# SPCE061A.net
KiCad netlist of a schematic drawn in Altium Designer
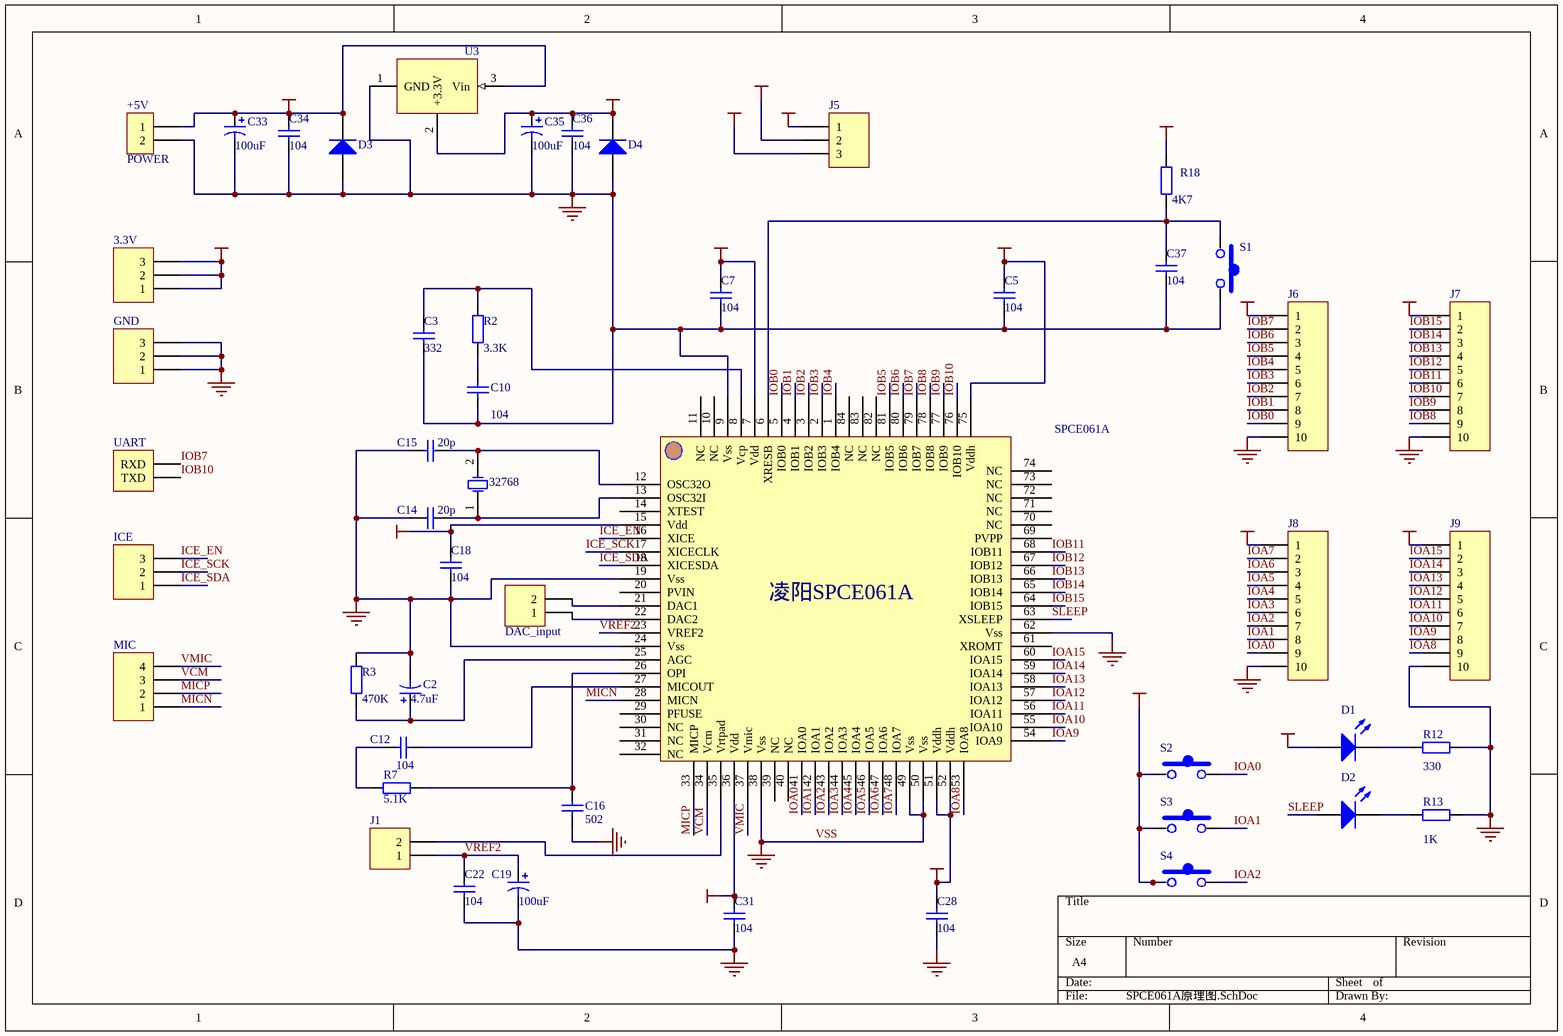
[diagram p0: SPCE061A原理图.SchDoc]

(export (version "E")
  (design (tool "Eeschema 10.0.6"))
  (components
    (comp (ref "+5V")
      (value "POWER")
      (footprint "zxcourhc:HDR-2")
      (libsource (lib "OldCow1 (1)") (part "POWER"))
    )
    (comp (ref "3.3V")
      (value "Header 3")
      (footprint "HDR1X3")
      (description "Header, 3-Pin")
      (fields (field (name "PUBLISHER") "Altium Limited"))
      (libsource (lib "Miscellaneous Connectors") (part "Header 3"))
    )
    (comp (ref "32768")
      (value "XTAL")
      (footprint "BCY-W2/D3.1")
      (description "Crystal Oscillator")
      (fields (field (name "PUBLISHER") "Altium Limited"))
      (libsource (lib "Miscellaneous Devices") (part "XTAL"))
    )
    (comp (ref "C2")
      (value "4.7uF")
      (footprint "zxcourhc:C-DJ-4")
      (description "Polarized Capacitor (Radial)")
      (fields (field (name "Comment") "Cap Pol1") (field (name "PUBLISHER") "Altium Limited"))
      (libsource (lib "Miscellaneous Devices") (part "Cap Pol1"))
    )
    (comp (ref "C3")
      (value "332")
      (footprint "Miscellaneous Devices:CAPR2.54-5.1x3.2")
      (description "Capacitor")
      (fields (field (name "Comment") "Cap") (field (name "PUBLISHER") "Altium Limited"))
      (libsource (lib "Miscellaneous Devices") (part "Cap"))
    )
    (comp (ref "C5")
      (value "104")
      (footprint "Miscellaneous Devices:CAPR2.54-5.1x3.2")
      (description "Capacitor")
      (fields (field (name "Comment") "Cap") (field (name "PUBLISHER") "Altium Limited"))
      (libsource (lib "Miscellaneous Devices") (part "Cap"))
    )
    (comp (ref "C7")
      (value "104")
      (footprint "Miscellaneous Devices:CAPR2.54-5.1x3.2")
      (description "Capacitor")
      (fields (field (name "Comment") "Cap") (field (name "PUBLISHER") "Altium Limited"))
      (libsource (lib "Miscellaneous Devices") (part "Cap"))
    )
    (comp (ref "C10")
      (value "104")
      (footprint "Miscellaneous Devices:CAPR2.54-5.1x3.2")
      (description "Capacitor")
      (fields (field (name "Comment") "Cap") (field (name "PUBLISHER") "Altium Limited"))
      (libsource (lib "Miscellaneous Devices") (part "Cap"))
    )
    (comp (ref "C12")
      (value "104")
      (footprint "Miscellaneous Devices:CAPR2.54-5.1x3.2")
      (description "Capacitor")
      (fields (field (name "Comment") "Cap") (field (name "PUBLISHER") "Altium Limited"))
      (libsource (lib "Miscellaneous Devices") (part "Cap"))
    )
    (comp (ref "C14")
      (value "20p")
      (footprint "Miscellaneous Devices:CAPR2.54-5.1x3.2")
      (description "Capacitor")
      (fields (field (name "Comment") "Cap") (field (name "PUBLISHER") "Altium Limited"))
      (libsource (lib "Miscellaneous Devices") (part "Cap"))
    )
    (comp (ref "C15")
      (value "20p")
      (footprint "Miscellaneous Devices:CAPR2.54-5.1x3.2")
      (description "Capacitor")
      (fields (field (name "Comment") "Cap") (field (name "PUBLISHER") "Altium Limited"))
      (libsource (lib "Miscellaneous Devices") (part "Cap"))
    )
    (comp (ref "C16")
      (value "502")
      (footprint "Miscellaneous Devices:CAPR2.54-5.1x3.2")
      (description "Capacitor")
      (fields (field (name "Comment") "Cap") (field (name "PUBLISHER") "Altium Limited"))
      (libsource (lib "Miscellaneous Devices") (part "Cap"))
    )
    (comp (ref "C18")
      (value "104")
      (footprint "Miscellaneous Devices:CAPR2.54-5.1x3.2")
      (description "Capacitor")
      (fields (field (name "Comment") "Cap") (field (name "PUBLISHER") "Altium Limited"))
      (libsource (lib "Miscellaneous Devices") (part "Cap"))
    )
    (comp (ref "C19")
      (value "100uF")
      (footprint "zxcourhc:C-DJ-4")
      (description "Polarized Capacitor (Radial)")
      (fields (field (name "Comment") "Cap Pol1") (field (name "PUBLISHER") "Altium Limited"))
      (libsource (lib "Miscellaneous Devices") (part "Cap Pol1"))
    )
    (comp (ref "C22")
      (value "104")
      (footprint "Miscellaneous Devices:CAPR2.54-5.1x3.2")
      (description "Capacitor")
      (fields (field (name "Comment") "Cap") (field (name "PUBLISHER") "Altium Limited"))
      (libsource (lib "Miscellaneous Devices") (part "Cap"))
    )
    (comp (ref "C28")
      (value "104")
      (footprint "Miscellaneous Devices:CAPR2.54-5.1x3.2")
      (description "Capacitor")
      (fields (field (name "Comment") "Cap") (field (name "PUBLISHER") "Altium Limited"))
      (libsource (lib "Miscellaneous Devices") (part "Cap"))
    )
    (comp (ref "C31")
      (value "104")
      (footprint "Miscellaneous Devices:CAPR2.54-5.1x3.2")
      (description "Capacitor")
      (fields (field (name "Comment") "Cap") (field (name "PUBLISHER") "Altium Limited"))
      (libsource (lib "Miscellaneous Devices") (part "Cap"))
    )
    (comp (ref "C33")
      (value "100uF")
      (footprint "zxcourhc:C-DJ-4")
      (description "Polarized Capacitor (Radial)")
      (fields (field (name "Comment") "Cap Pol1") (field (name "PUBLISHER") "Altium Limited"))
      (libsource (lib "Miscellaneous Devices") (part "Cap Pol1"))
    )
    (comp (ref "C34")
      (value "104")
      (footprint "Miscellaneous Devices:CAPR2.54-5.1x3.2")
      (description "Capacitor")
      (fields (field (name "Comment") "Cap") (field (name "PUBLISHER") "Altium Limited"))
      (libsource (lib "Miscellaneous Devices") (part "Cap"))
    )
    (comp (ref "C35")
      (value "100uF")
      (footprint "zxcourhc:C-DJ-4")
      (description "Polarized Capacitor (Radial)")
      (fields (field (name "Comment") "Cap Pol1") (field (name "PUBLISHER") "Altium Limited"))
      (libsource (lib "Miscellaneous Devices") (part "Cap Pol1"))
    )
    (comp (ref "C36")
      (value "104")
      (footprint "Miscellaneous Devices:CAPR2.54-5.1x3.2")
      (description "Capacitor")
      (fields (field (name "Comment") "Cap") (field (name "PUBLISHER") "Altium Limited"))
      (libsource (lib "Miscellaneous Devices") (part "Cap"))
    )
    (comp (ref "C37")
      (value "104")
      (footprint "Miscellaneous Devices:CAPR2.54-5.1x3.2")
      (description "Capacitor")
      (fields (field (name "Comment") "Cap") (field (name "PUBLISHER") "Altium Limited"))
      (libsource (lib "Miscellaneous Devices") (part "Cap"))
    )
    (comp (ref "D1")
      (value "LED3")
      (footprint "SMD _LED")
      (description "Typical BLUE SiC LED")
      (fields (field (name "PUBLISHER") "Altium Limited"))
      (libsource (lib "Miscellaneous Devices") (part "LED3"))
    )
    (comp (ref "D2")
      (value "LED3")
      (footprint "SMD _LED")
      (description "Typical BLUE SiC LED")
      (fields (field (name "PUBLISHER") "Altium Limited"))
      (libsource (lib "Miscellaneous Devices") (part "LED3"))
    )
    (comp (ref "D3")
      (value "Diode 1N4148")
      (footprint "DIO7.1-3.9x1.9")
      (description "High Conductance Fast Diode")
      (fields (field (name "PUBLISHER") "Altium Limited"))
      (libsource (lib "Miscellaneous Devices") (part "Diode 1N4148"))
    )
    (comp (ref "D4")
      (value "Diode 1N4148")
      (footprint "DIO7.1-3.9x1.9")
      (description "High Conductance Fast Diode")
      (fields (field (name "PUBLISHER") "Altium Limited"))
      (libsource (lib "Miscellaneous Devices") (part "Diode 1N4148"))
    )
    (comp (ref "DAC_input")
      (value "Header 2")
      (footprint "HDR1X2")
      (description "Header, 2-Pin")
      (fields (field (name "PUBLISHER") "Altium Limited"))
      (libsource (lib "Miscellaneous Connectors") (part "Header 2"))
    )
    (comp (ref "GND")
      (value "Header 3")
      (footprint "HDR1X3")
      (description "Header, 3-Pin")
      (fields (field (name "PUBLISHER") "Altium Limited"))
      (libsource (lib "Miscellaneous Connectors") (part "Header 3"))
    )
    (comp (ref "ICE")
      (value "Header 3")
      (footprint "HDR1X3")
      (description "Header, 3-Pin")
      (fields (field (name "PUBLISHER") "Altium Limited"))
      (libsource (lib "Miscellaneous Connectors") (part "Header 3"))
    )
    (comp (ref "J1")
      (value "Header 2")
      (footprint "HDR1X2")
      (description "Header, 2-Pin")
      (fields (field (name "PUBLISHER") "Altium Limited"))
      (libsource (lib "Miscellaneous Connectors") (part "Header 2"))
    )
    (comp (ref "J5")
      (value "Header 3")
      (footprint "HDR1X3")
      (description "Header, 3-Pin")
      (fields (field (name "PUBLISHER") "Altium Limited"))
      (libsource (lib "") (part "Header 3_1"))
    )
    (comp (ref "J6")
      (value "IOB0~IOB7")
      (footprint "HDR1X10")
      (description "Header, 10-Pin")
      (fields (field (name "PUBLISHER") "Altium Limited"))
      (libsource (lib "Miscellaneous Connectors") (part "Header 10"))
    )
    (comp (ref "J7")
      (value "IOB8~IOB15")
      (footprint "HDR1X10")
      (description "Header, 10-Pin")
      (fields (field (name "PUBLISHER") "Altium Limited"))
      (libsource (lib "Miscellaneous Connectors") (part "Header 10"))
    )
    (comp (ref "J8")
      (value "IOA0~IOA7")
      (footprint "HDR1X10")
      (description "Header, 10-Pin")
      (fields (field (name "PUBLISHER") "Altium Limited"))
      (libsource (lib "Miscellaneous Connectors") (part "Header 10"))
    )
    (comp (ref "J9")
      (value "IOA8~IOA15")
      (footprint "HDR1X10")
      (description "Header, 10-Pin")
      (fields (field (name "PUBLISHER") "Altium Limited"))
      (libsource (lib "Miscellaneous Connectors") (part "Header 10"))
    )
    (comp (ref "MIC")
      (value "Header 4")
      (footprint "HDR1X4")
      (description "Header, 4-Pin")
      (fields (field (name "PUBLISHER") "Altium Limited"))
      (libsource (lib "Miscellaneous Connectors") (part "Header 4"))
    )
    (comp (ref "R2")
      (value "3.3K")
      (footprint "AXIAL-0.4")
      (description "Resistor")
      (fields (field (name "Comment") "Res2") (field (name "PUBLISHER") "Altium Limited"))
      (libsource (lib "") (part "Res2_2"))
    )
    (comp (ref "R3")
      (value "470K")
      (footprint "AXIAL-0.4")
      (description "Resistor")
      (fields (field (name "Comment") "Res2") (field (name "PUBLISHER") "Altium Limited"))
      (libsource (lib "") (part "Res2_2"))
    )
    (comp (ref "R7")
      (value "5.1K")
      (footprint "AXIAL-0.4")
      (description "Resistor")
      (fields (field (name "Comment") "Res2") (field (name "PUBLISHER") "Altium Limited"))
      (libsource (lib "") (part "Res2_1"))
    )
    (comp (ref "R12")
      (value "330")
      (footprint "AXIAL-0.4")
      (description "Resistor")
      (fields (field (name "Comment") "Res2") (field (name "PUBLISHER") "Altium Limited"))
      (libsource (lib "Miscellaneous Devices") (part "Res2"))
    )
    (comp (ref "R13")
      (value "1K")
      (footprint "AXIAL-0.4")
      (description "Resistor")
      (fields (field (name "Comment") "Res2") (field (name "PUBLISHER") "Altium Limited"))
      (libsource (lib "Miscellaneous Devices") (part "Res2"))
    )
    (comp (ref "R18")
      (value "4K7")
      (footprint "AXIAL-0.4")
      (description "Resistor")
      (fields (field (name "Comment") "Res2") (field (name "PUBLISHER") "Altium Limited"))
      (libsource (lib "") (part "Res2_2"))
    )
    (comp (ref "S1") (value "KEY") (footprint "an-6*6") (libsource (lib "OldCow1 (1)") (part "KEY")))
    (comp (ref "S2")
      (value "KEY2")
      (footprint "zxcourhc:an-6*6")
      (libsource (lib "OldCow1 (1)") (part "KEY"))
    )
    (comp (ref "S3") (value "KEY3") (footprint "an-6*6") (libsource (lib "OldCow1 (1)") (part "KEY")))
    (comp (ref "S4") (value "KEY4") (footprint "an-6*6") (libsource (lib "OldCow1 (1)") (part "KEY")))
    (comp (ref "SPCE061A")
      (value "PLCC84")
      (footprint "SPCE061A_PLCC84")
      (libsource (lib "SPCE061A") (part "SPCE061A_PLCC84"))
    )
    (comp (ref "U3") (value "LM7833") (footprint "A1117") (libsource (lib "MyInt_Lib") (part "LM7805CT")))
    (comp (ref "UART")
      (value "Header 2")
      (footprint "HDR1X2")
      (description "Header, 2-Pin")
      (fields (field (name "PUBLISHER") "Altium Limited"))
      (libsource (lib "Miscellaneous Connectors") (part "Header 2"))
    )
  )
  (nets
    (net (code "1") (name "/ICE_EN") (class "Default")
      (node (ref "ICE") (pin "3") (pinfunction "3_3") (pintype "passive"))
      (node (ref "SPCE061A") (pin "16") (pinfunction "XICE_16") (pintype "passive"))
    )
    (net (code "2") (name "/ICE_SCK") (class "Default")
      (node (ref "ICE") (pin "2") (pinfunction "2_2") (pintype "passive"))
      (node (ref "SPCE061A") (pin "17") (pinfunction "XICECLK_17") (pintype "passive"))
    )
    (net (code "3") (name "/ICE_SDA") (class "Default")
      (node (ref "ICE") (pin "1") (pinfunction "1_1") (pintype "passive"))
      (node (ref "SPCE061A") (pin "18") (pinfunction "XICESDA_18") (pintype "passive"))
    )
    (net (code "4") (name "/IOA0") (class "Default")
      (node (ref "J8") (pin "9") (pinfunction "9_9") (pintype "passive"))
      (node (ref "S2") (pin "2") (pinfunction "2_2") (pintype "passive"))
      (node (ref "SPCE061A") (pin "41") (pinfunction "IOA0_41") (pintype "passive"))
    )
    (net (code "5") (name "/IOA1") (class "Default")
      (node (ref "J8") (pin "8") (pinfunction "8_8") (pintype "passive"))
      (node (ref "S3") (pin "2") (pinfunction "2_2") (pintype "passive"))
      (node (ref "SPCE061A") (pin "42") (pinfunction "IOA1_42") (pintype "passive"))
    )
    (net (code "6") (name "/IOA2") (class "Default")
      (node (ref "J8") (pin "7") (pinfunction "7_7") (pintype "passive"))
      (node (ref "S4") (pin "2") (pinfunction "2_2") (pintype "passive"))
      (node (ref "SPCE061A") (pin "43") (pinfunction "IOA2_43") (pintype "passive"))
    )
    (net (code "7") (name "/IOA3") (class "Default")
      (node (ref "J8") (pin "6") (pinfunction "6_6") (pintype "passive"))
      (node (ref "SPCE061A") (pin "44") (pinfunction "IOA3_44") (pintype "passive"))
    )
    (net (code "8") (name "/IOA4") (class "Default")
      (node (ref "J8") (pin "5") (pinfunction "5_5") (pintype "passive"))
      (node (ref "SPCE061A") (pin "45") (pinfunction "IOA4_45") (pintype "passive"))
    )
    (net (code "9") (name "/IOA5") (class "Default")
      (node (ref "J8") (pin "4") (pinfunction "4_4") (pintype "passive"))
      (node (ref "SPCE061A") (pin "46") (pinfunction "IOA5_46") (pintype "passive"))
    )
    (net (code "10") (name "/IOA6") (class "Default")
      (node (ref "J8") (pin "3") (pinfunction "3_3") (pintype "passive"))
      (node (ref "SPCE061A") (pin "47") (pinfunction "IOA6_47") (pintype "passive"))
    )
    (net (code "11") (name "/IOA7") (class "Default")
      (node (ref "J8") (pin "2") (pinfunction "2_2") (pintype "passive"))
      (node (ref "SPCE061A") (pin "48") (pinfunction "IOA7_48") (pintype "passive"))
    )
    (net (code "12") (name "/IOA8") (class "Default")
      (node (ref "J9") (pin "9") (pinfunction "9_9") (pintype "passive"))
      (node (ref "SPCE061A") (pin "53") (pinfunction "IOA8_53") (pintype "passive"))
    )
    (net (code "13") (name "/IOA9") (class "Default")
      (node (ref "J9") (pin "8") (pinfunction "8_8") (pintype "passive"))
      (node (ref "SPCE061A") (pin "54") (pinfunction "IOA9_54") (pintype "passive"))
    )
    (net (code "14") (name "/IOA10") (class "Default")
      (node (ref "J9") (pin "7") (pinfunction "7_7") (pintype "passive"))
      (node (ref "SPCE061A") (pin "55") (pinfunction "IOA10_55") (pintype "passive"))
    )
    (net (code "15") (name "/IOA11") (class "Default")
      (node (ref "J9") (pin "6") (pinfunction "6_6") (pintype "passive"))
      (node (ref "SPCE061A") (pin "56") (pinfunction "IOA11_56") (pintype "passive"))
    )
    (net (code "16") (name "/IOA12") (class "Default")
      (node (ref "J9") (pin "5") (pinfunction "5_5") (pintype "passive"))
      (node (ref "SPCE061A") (pin "57") (pinfunction "IOA12_57") (pintype "passive"))
    )
    (net (code "17") (name "/IOA13") (class "Default")
      (node (ref "J9") (pin "4") (pinfunction "4_4") (pintype "passive"))
      (node (ref "SPCE061A") (pin "58") (pinfunction "IOA13_58") (pintype "passive"))
    )
    (net (code "18") (name "/IOA14") (class "Default")
      (node (ref "J9") (pin "3") (pinfunction "3_3") (pintype "passive"))
      (node (ref "SPCE061A") (pin "59") (pinfunction "IOA14_59") (pintype "passive"))
    )
    (net (code "19") (name "/IOA15") (class "Default")
      (node (ref "J9") (pin "2") (pinfunction "2_2") (pintype "passive"))
      (node (ref "SPCE061A") (pin "60") (pinfunction "IOA15_60") (pintype "passive"))
    )
    (net (code "20") (name "/IOB0") (class "Default")
      (node (ref "J6") (pin "9") (pinfunction "9_9") (pintype "passive"))
      (node (ref "SPCE061A") (pin "5") (pinfunction "IOB0_5") (pintype "passive"))
    )
    (net (code "21") (name "/IOB1") (class "Default")
      (node (ref "J6") (pin "8") (pinfunction "8_8") (pintype "passive"))
      (node (ref "SPCE061A") (pin "4") (pinfunction "IOB1_4") (pintype "passive"))
    )
    (net (code "22") (name "/IOB2") (class "Default")
      (node (ref "J6") (pin "7") (pinfunction "7_7") (pintype "passive"))
      (node (ref "SPCE061A") (pin "3") (pinfunction "IOB2_3") (pintype "passive"))
    )
    (net (code "23") (name "/IOB3") (class "Default")
      (node (ref "J6") (pin "6") (pinfunction "6_6") (pintype "passive"))
      (node (ref "SPCE061A") (pin "2") (pinfunction "IOB3_2") (pintype "passive"))
    )
    (net (code "24") (name "/IOB4") (class "Default")
      (node (ref "J6") (pin "5") (pinfunction "5_5") (pintype "passive"))
      (node (ref "SPCE061A") (pin "1") (pinfunction "IOB4_1") (pintype "passive"))
    )
    (net (code "25") (name "/IOB5") (class "Default")
      (node (ref "J6") (pin "4") (pinfunction "4_4") (pintype "passive"))
      (node (ref "SPCE061A") (pin "81") (pinfunction "IOB5_81") (pintype "passive"))
    )
    (net (code "26") (name "/IOB6") (class "Default")
      (node (ref "J6") (pin "3") (pinfunction "3_3") (pintype "passive"))
      (node (ref "SPCE061A") (pin "80") (pinfunction "IOB6_80") (pintype "passive"))
    )
    (net (code "27") (name "/IOB7") (class "Default")
      (node (ref "J6") (pin "2") (pinfunction "2_2") (pintype "passive"))
      (node (ref "SPCE061A") (pin "79") (pinfunction "IOB7_79") (pintype "passive"))
      (node (ref "UART") (pin "2") (pinfunction "RXD_2") (pintype "passive"))
    )
    (net (code "28") (name "/IOB8") (class "Default")
      (node (ref "J7") (pin "9") (pinfunction "9_9") (pintype "passive"))
      (node (ref "SPCE061A") (pin "78") (pinfunction "IOB8_78") (pintype "passive"))
    )
    (net (code "29") (name "/IOB9") (class "Default")
      (node (ref "J7") (pin "8") (pinfunction "8_8") (pintype "passive"))
      (node (ref "SPCE061A") (pin "77") (pinfunction "IOB9_77") (pintype "passive"))
    )
    (net (code "30") (name "/IOB10") (class "Default")
      (node (ref "J7") (pin "7") (pinfunction "7_7") (pintype "passive"))
      (node (ref "SPCE061A") (pin "76") (pinfunction "IOB10_76") (pintype "passive"))
      (node (ref "UART") (pin "1") (pinfunction "TXD_1") (pintype "passive"))
    )
    (net (code "31") (name "/IOB11") (class "Default")
      (node (ref "J7") (pin "6") (pinfunction "6_6") (pintype "passive"))
      (node (ref "SPCE061A") (pin "68") (pinfunction "IOB11_68") (pintype "passive"))
    )
    (net (code "32") (name "/IOB12") (class "Default")
      (node (ref "J7") (pin "5") (pinfunction "5_5") (pintype "passive"))
      (node (ref "SPCE061A") (pin "67") (pinfunction "IOB12_67") (pintype "passive"))
    )
    (net (code "33") (name "/IOB13") (class "Default")
      (node (ref "J7") (pin "4") (pinfunction "4_4") (pintype "passive"))
      (node (ref "SPCE061A") (pin "66") (pinfunction "IOB13_66") (pintype "passive"))
    )
    (net (code "34") (name "/IOB14") (class "Default")
      (node (ref "J7") (pin "3") (pinfunction "3_3") (pintype "passive"))
      (node (ref "SPCE061A") (pin "65") (pinfunction "IOB14_65") (pintype "passive"))
    )
    (net (code "35") (name "/IOB15") (class "Default")
      (node (ref "J7") (pin "2") (pinfunction "2_2") (pintype "passive"))
      (node (ref "SPCE061A") (pin "64") (pinfunction "IOB15_64") (pintype "passive"))
    )
    (net (code "36") (name "/MICN") (class "Default")
      (node (ref "MIC") (pin "1") (pinfunction "1_1") (pintype "passive"))
      (node (ref "SPCE061A") (pin "28") (pinfunction "MICN_28") (pintype "passive"))
    )
    (net (code "37") (name "/MICP") (class "Default")
      (node (ref "MIC") (pin "2") (pinfunction "2_2") (pintype "passive"))
      (node (ref "SPCE061A") (pin "33") (pinfunction "MICP_33") (pintype "passive"))
    )
    (net (code "38") (name "/SLEEP") (class "Default")
      (node (ref "D2") (pin "1") (pinfunction "A_1") (pintype "passive"))
      (node (ref "SPCE061A") (pin "63") (pinfunction "XSLEEP_63") (pintype "passive"))
    )
    (net (code "39") (name "/VCM") (class "Default")
      (node (ref "MIC") (pin "3") (pinfunction "3_3") (pintype "passive"))
      (node (ref "SPCE061A") (pin "34") (pinfunction "Vcm_34") (pintype "passive"))
    )
    (net (code "40") (name "/VMIC") (class "Default")
      (node (ref "MIC") (pin "4") (pinfunction "4_4") (pintype "passive"))
      (node (ref "SPCE061A") (pin "37") (pinfunction "Vmic_37") (pintype "passive"))
    )
    (net (code "41") (name "/VREF2") (class "Default")
      (node (ref "C19") (pin "1") (pinfunction "1_1") (pintype "passive"))
      (node (ref "C22") (pin "2") (pinfunction "2_2") (pintype "passive"))
      (node (ref "J1") (pin "1") (pinfunction "TXD_1") (pintype "passive"))
      (node (ref "SPCE061A") (pin "23") (pinfunction "VREF2_23") (pintype "passive"))
    )
    (net (code "42") (name "Net-(32768-OSC1)") (class "Default")
      (node (ref "32768") (pin "1") (pinfunction "OSC1_1") (pintype "passive"))
      (node (ref "C14") (pin "2") (pinfunction "2_2") (pintype "passive"))
      (node (ref "SPCE061A") (pin "13") (pinfunction "OSC32I_13") (pintype "passive"))
    )
    (net (code "43") (name "Net-(32768-OSC2)") (class "Default")
      (node (ref "32768") (pin "2") (pinfunction "OSC2_2") (pintype "passive"))
      (node (ref "C15") (pin "1") (pinfunction "1_1") (pintype "passive"))
      (node (ref "SPCE061A") (pin "12") (pinfunction "OSC32O_12") (pintype "passive"))
    )
    (net (code "44") (name "Net-(C10-Pad2)") (class "Default")
      (node (ref "C10") (pin "2") (pinfunction "2_2") (pintype "passive"))
      (node (ref "R2") (pin "1") (pinfunction "1_1") (pintype "passive"))
    )
    (net (code "45") (name "Net-(C12-Pad2)") (class "Default")
      (node (ref "C12") (pin "2") (pinfunction "2_2") (pintype "passive"))
      (node (ref "R7") (pin "2") (pinfunction "2_2") (pintype "passive"))
    )
    (net (code "46") (name "Net-(D1-K)") (class "Default")
      (node (ref "D1") (pin "2") (pinfunction "K_2") (pintype "passive"))
      (node (ref "R12") (pin "1") (pinfunction "1_1") (pintype "passive"))
    )
    (net (code "47") (name "Net-(D2-K)") (class "Default")
      (node (ref "D2") (pin "2") (pinfunction "K_2") (pintype "passive"))
      (node (ref "R13") (pin "1") (pinfunction "1_1") (pintype "passive"))
    )
    (net (code "48") (name "Net-(DAC_input-RXD)") (class "Default")
      (node (ref "DAC_input") (pin "2") (pinfunction "RXD_2") (pintype "passive"))
      (node (ref "SPCE061A") (pin "21") (pinfunction "DAC1_21") (pintype "passive"))
    )
    (net (code "49") (name "Net-(DAC_input-TXD)") (class "Default")
      (node (ref "DAC_input") (pin "1") (pinfunction "TXD_1") (pintype "passive"))
      (node (ref "SPCE061A") (pin "22") (pinfunction "DAC2_22") (pintype "passive"))
    )
    (net (code "50") (name "Net-(J1-RXD)") (class "Default")
      (node (ref "J1") (pin "2") (pinfunction "RXD_2") (pintype "passive"))
      (node (ref "SPCE061A") (pin "35") (pinfunction "Vrtpad_35") (pintype "passive"))
    )
    (net (code "51") (name "Net-(SPCE061A-AGC)") (class "Default")
      (node (ref "C2") (pin "1") (pinfunction "1_1") (pintype "passive"))
      (node (ref "R3") (pin "1") (pinfunction "1_1") (pintype "passive"))
      (node (ref "SPCE061A") (pin "25") (pinfunction "AGC_25") (pintype "passive"))
    )
    (net (code "52") (name "Net-(SPCE061A-MICOUT)") (class "Default")
      (node (ref "C12") (pin "1") (pinfunction "1_1") (pintype "passive"))
      (node (ref "SPCE061A") (pin "27") (pinfunction "MICOUT_27") (pintype "passive"))
    )
    (net (code "53") (name "Net-(SPCE061A-OPI)") (class "Default")
      (node (ref "C16") (pin "1") (pinfunction "1_1") (pintype "passive"))
      (node (ref "R7") (pin "1") (pinfunction "1_1") (pintype "passive"))
      (node (ref "SPCE061A") (pin "26") (pinfunction "OPI_26") (pintype "passive"))
    )
    (net (code "54") (name "Net-(SPCE061A-Vcp)") (class "Default")
      (node (ref "C3") (pin "2") (pinfunction "2_2") (pintype "passive"))
      (node (ref "R2") (pin "2") (pinfunction "2_2") (pintype "passive"))
      (node (ref "SPCE061A") (pin "8") (pinfunction "Vcp_8") (pintype "passive"))
    )
    (net (code "55") (name "Net-(SPCE061A-XRESB)") (class "Default")
      (node (ref "C37") (pin "1") (pinfunction "1_1") (pintype "passive"))
      (node (ref "R18") (pin "1") (pinfunction "1_1") (pintype "passive"))
      (node (ref "S1") (pin "1") (pinfunction "1_1") (pintype "passive"))
      (node (ref "SPCE061A") (pin "6") (pinfunction "XRESB_6") (pintype "passive"))
    )
    (net (code "56") (name "V5") (class "Default")
      (node (ref "+5V") (pin "1") (pinfunction "1_1") (pintype "passive"))
      (node (ref "C33") (pin "1") (pinfunction "1_1") (pintype "passive"))
      (node (ref "C34") (pin "2") (pinfunction "2_2") (pintype "passive"))
      (node (ref "D3") (pin "2") (pinfunction "K_2") (pintype "passive"))
      (node (ref "J5") (pin "1") (pinfunction "1_1") (pintype "passive"))
      (node (ref "S2") (pin "1") (pinfunction "1_1") (pintype "passive"))
      (node (ref "S3") (pin "1") (pinfunction "1_1") (pintype "passive"))
      (node (ref "S4") (pin "1") (pinfunction "1_1") (pintype "passive"))
      (node (ref "U3") (pin "3") (pinfunction "Vin_3") (pintype "input"))
    )
    (net (code "57") (name "VDD") (class "Default")
      (node (ref "3.3V") (pin "1") (pinfunction "1_1") (pintype "passive"))
      (node (ref "3.3V") (pin "2") (pinfunction "2_2") (pintype "passive"))
      (node (ref "3.3V") (pin "3") (pinfunction "3_3") (pintype "passive"))
      (node (ref "C18") (pin "2") (pinfunction "2_2") (pintype "passive"))
      (node (ref "C31") (pin "2") (pinfunction "2_2") (pintype "passive"))
      (node (ref "C35") (pin "1") (pinfunction "1_1") (pintype "passive"))
      (node (ref "C36") (pin "2") (pinfunction "2_2") (pintype "passive"))
      (node (ref "C7") (pin "2") (pinfunction "2_2") (pintype "passive"))
      (node (ref "D1") (pin "1") (pinfunction "A_1") (pintype "passive"))
      (node (ref "D4") (pin "2") (pinfunction "K_2") (pintype "passive"))
      (node (ref "J5") (pin "3") (pinfunction "3_3") (pintype "passive"))
      (node (ref "R18") (pin "2") (pinfunction "2_2") (pintype "passive"))
      (node (ref "SPCE061A") (pin "15") (pinfunction "Vdd_15") (pintype "passive"))
      (node (ref "SPCE061A") (pin "36") (pinfunction "Vdd_36") (pintype "passive"))
      (node (ref "SPCE061A") (pin "7") (pinfunction "Vdd_7") (pintype "passive"))
      (node (ref "U3") (pin "2") (pinfunction "+3.3V_2") (pintype "power_in"))
    )
    (net (code "58") (name "VDDH") (class "Default")
      (node (ref "C28") (pin "2") (pinfunction "2_2") (pintype "passive"))
      (node (ref "C5") (pin "2") (pinfunction "2_2") (pintype "passive"))
      (node (ref "J5") (pin "2") (pinfunction "2_2") (pintype "passive"))
      (node (ref "J6") (pin "1") (pinfunction "1_1") (pintype "passive"))
      (node (ref "J7") (pin "1") (pinfunction "1_1") (pintype "passive"))
      (node (ref "J8") (pin "1") (pinfunction "1_1") (pintype "passive"))
      (node (ref "J9") (pin "1") (pinfunction "1_1") (pintype "passive"))
      (node (ref "SPCE061A") (pin "51") (pinfunction "Vddh_51") (pintype "passive"))
      (node (ref "SPCE061A") (pin "52") (pinfunction "Vddh_52") (pintype "passive"))
      (node (ref "SPCE061A") (pin "75") (pinfunction "Vddh_75") (pintype "passive"))
    )
    (net (code "59") (name "VSS") (class "Default")
      (node (ref "+5V") (pin "2") (pinfunction "2_2") (pintype "passive"))
      (node (ref "C10") (pin "1") (pinfunction "1_1") (pintype "passive"))
      (node (ref "C14") (pin "1") (pinfunction "1_1") (pintype "passive"))
      (node (ref "C15") (pin "2") (pinfunction "2_2") (pintype "passive"))
      (node (ref "C16") (pin "2") (pinfunction "2_2") (pintype "passive"))
      (node (ref "C18") (pin "1") (pinfunction "1_1") (pintype "passive"))
      (node (ref "C19") (pin "2") (pinfunction "2_2") (pintype "passive"))
      (node (ref "C2") (pin "2") (pinfunction "2_2") (pintype "passive"))
      (node (ref "C22") (pin "1") (pinfunction "1_1") (pintype "passive"))
      (node (ref "C28") (pin "1") (pinfunction "1_1") (pintype "passive"))
      (node (ref "C3") (pin "1") (pinfunction "1_1") (pintype "passive"))
      (node (ref "C31") (pin "1") (pinfunction "1_1") (pintype "passive"))
      (node (ref "C33") (pin "2") (pinfunction "2_2") (pintype "passive"))
      (node (ref "C34") (pin "1") (pinfunction "1_1") (pintype "passive"))
      (node (ref "C35") (pin "2") (pinfunction "2_2") (pintype "passive"))
      (node (ref "C36") (pin "1") (pinfunction "1_1") (pintype "passive"))
      (node (ref "C37") (pin "2") (pinfunction "2_2") (pintype "passive"))
      (node (ref "C5") (pin "1") (pinfunction "1_1") (pintype "passive"))
      (node (ref "C7") (pin "1") (pinfunction "1_1") (pintype "passive"))
      (node (ref "D3") (pin "1") (pinfunction "A_1") (pintype "passive"))
      (node (ref "D4") (pin "1") (pinfunction "A_1") (pintype "passive"))
      (node (ref "GND") (pin "1") (pinfunction "1_1") (pintype "passive"))
      (node (ref "GND") (pin "2") (pinfunction "2_2") (pintype "passive"))
      (node (ref "GND") (pin "3") (pinfunction "3_3") (pintype "passive"))
      (node (ref "J6") (pin "10") (pinfunction "10_10") (pintype "passive"))
      (node (ref "J7") (pin "10") (pinfunction "10_10") (pintype "passive"))
      (node (ref "J8") (pin "10") (pinfunction "10_10") (pintype "passive"))
      (node (ref "J9") (pin "10") (pinfunction "10_10") (pintype "passive"))
      (node (ref "R12") (pin "2") (pinfunction "2_2") (pintype "passive"))
      (node (ref "R13") (pin "2") (pinfunction "2_2") (pintype "passive"))
      (node (ref "R3") (pin "2") (pinfunction "2_2") (pintype "passive"))
      (node (ref "S1") (pin "2") (pinfunction "2_2") (pintype "passive"))
      (node (ref "SPCE061A") (pin "19") (pinfunction "Vss_19") (pintype "passive"))
      (node (ref "SPCE061A") (pin "24") (pinfunction "Vss_24") (pintype "passive"))
      (node (ref "SPCE061A") (pin "38") (pinfunction "Vss_38") (pintype "passive"))
      (node (ref "SPCE061A") (pin "49") (pinfunction "Vss_49") (pintype "passive"))
      (node (ref "SPCE061A") (pin "50") (pinfunction "Vss_50") (pintype "passive"))
      (node (ref "SPCE061A") (pin "62") (pinfunction "Vss_62") (pintype "passive"))
      (node (ref "SPCE061A") (pin "9") (pinfunction "Vss_9") (pintype "passive"))
      (node (ref "U3") (pin "1") (pinfunction "GND_1") (pintype "power_in"))
    )
    (net (code "60") (name "unconnected-(SPCE061A-NC-Pad10)") (class "Default")
      (node (ref "SPCE061A") (pin "10") (pinfunction "NC_10") (pintype "passive"))
    )
    (net (code "61") (name "unconnected-(SPCE061A-NC-Pad11)") (class "Default")
      (node (ref "SPCE061A") (pin "11") (pinfunction "NC_11") (pintype "passive"))
    )
    (net (code "62") (name "unconnected-(SPCE061A-NC-Pad30)") (class "Default")
      (node (ref "SPCE061A") (pin "30") (pinfunction "NC_30") (pintype "passive"))
    )
    (net (code "63") (name "unconnected-(SPCE061A-NC-Pad31)") (class "Default")
      (node (ref "SPCE061A") (pin "31") (pinfunction "NC_31") (pintype "passive"))
    )
    (net (code "64") (name "unconnected-(SPCE061A-NC-Pad32)") (class "Default")
      (node (ref "SPCE061A") (pin "32") (pinfunction "NC_32") (pintype "passive"))
    )
    (net (code "65") (name "unconnected-(SPCE061A-NC-Pad39)") (class "Default")
      (node (ref "SPCE061A") (pin "39") (pinfunction "NC_39") (pintype "passive"))
    )
    (net (code "66") (name "unconnected-(SPCE061A-NC-Pad40)") (class "Default")
      (node (ref "SPCE061A") (pin "40") (pinfunction "NC_40") (pintype "passive"))
    )
    (net (code "67") (name "unconnected-(SPCE061A-NC-Pad70)") (class "Default")
      (node (ref "SPCE061A") (pin "70") (pinfunction "NC_70") (pintype "passive"))
    )
    (net (code "68") (name "unconnected-(SPCE061A-NC-Pad71)") (class "Default")
      (node (ref "SPCE061A") (pin "71") (pinfunction "NC_71") (pintype "passive"))
    )
    (net (code "69") (name "unconnected-(SPCE061A-NC-Pad72)") (class "Default")
      (node (ref "SPCE061A") (pin "72") (pinfunction "NC_72") (pintype "passive"))
    )
    (net (code "70") (name "unconnected-(SPCE061A-NC-Pad73)") (class "Default")
      (node (ref "SPCE061A") (pin "73") (pinfunction "NC_73") (pintype "passive"))
    )
    (net (code "71") (name "unconnected-(SPCE061A-NC-Pad74)") (class "Default")
      (node (ref "SPCE061A") (pin "74") (pinfunction "NC_74") (pintype "passive"))
    )
    (net (code "72") (name "unconnected-(SPCE061A-NC-Pad82)") (class "Default")
      (node (ref "SPCE061A") (pin "82") (pinfunction "NC_82") (pintype "passive"))
    )
    (net (code "73") (name "unconnected-(SPCE061A-NC-Pad83)") (class "Default")
      (node (ref "SPCE061A") (pin "83") (pinfunction "NC_83") (pintype "passive"))
    )
    (net (code "74") (name "unconnected-(SPCE061A-NC-Pad84)") (class "Default")
      (node (ref "SPCE061A") (pin "84") (pinfunction "NC_84") (pintype "passive"))
    )
    (net (code "75") (name "unconnected-(SPCE061A-PFUSE-Pad29)") (class "Default")
      (node (ref "SPCE061A") (pin "29") (pinfunction "PFUSE_29") (pintype "passive"))
    )
    (net (code "76") (name "unconnected-(SPCE061A-PVIN-Pad20)") (class "Default")
      (node (ref "SPCE061A") (pin "20") (pinfunction "PVIN_20") (pintype "passive"))
    )
    (net (code "77") (name "unconnected-(SPCE061A-PVPP-Pad69)") (class "Default")
      (node (ref "SPCE061A") (pin "69") (pinfunction "PVPP_69") (pintype "passive"))
    )
    (net (code "78") (name "unconnected-(SPCE061A-XROMT-Pad61)") (class "Default")
      (node (ref "SPCE061A") (pin "61") (pinfunction "XROMT_61") (pintype "passive"))
    )
    (net (code "79") (name "unconnected-(SPCE061A-XTEST-Pad14)") (class "Default")
      (node (ref "SPCE061A") (pin "14") (pinfunction "XTEST_14") (pintype "passive"))
    )
  )
)
